# motor_controller_rev_3_0_6.net
KiCad netlist of a schematic drawn in EAGLE
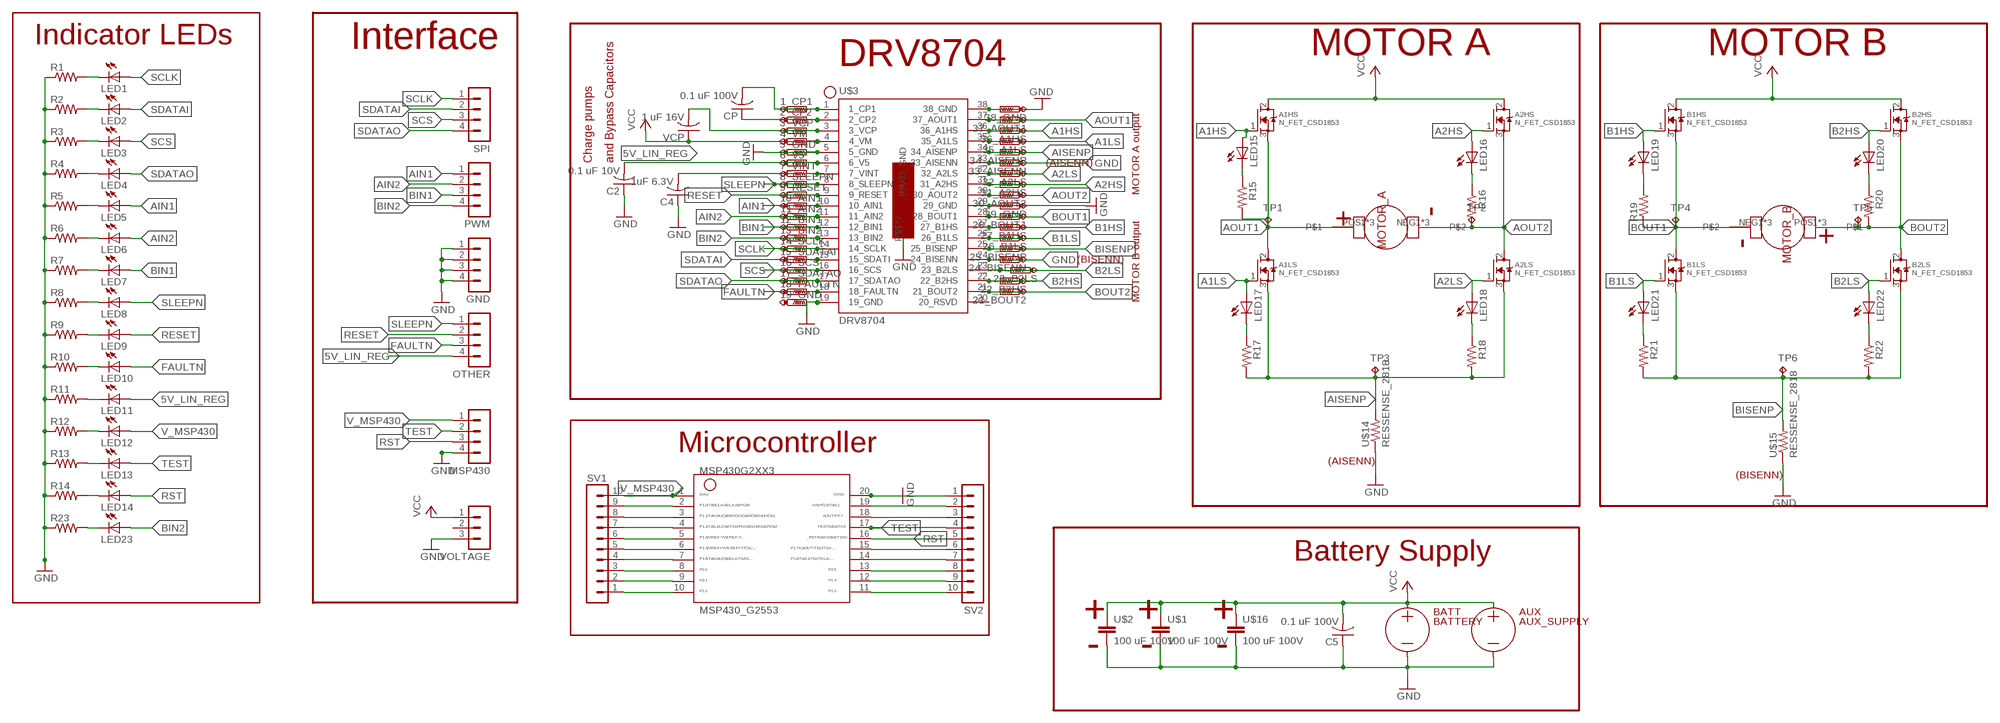
[diagram p0: schematic, sheet 1]

(export (version "E")
  (design (tool "Eeschema 10.0.6"))
  (components
    (comp (ref "1_CP1")
      (value "PTR1TP10R")
      (footprint "eagle-import:TP10R")
      (libsource (lib "eagle-import") (part "PTR1TP10R"))
    )
    (comp (ref "2_CP2")
      (value "PTR1TP10R")
      (footprint "eagle-import:TP10R")
      (libsource (lib "eagle-import") (part "PTR1TP10R"))
    )
    (comp (ref "3_VCP")
      (value "PTR1TP10R")
      (footprint "eagle-import:TP10R")
      (libsource (lib "eagle-import") (part "PTR1TP10R"))
    )
    (comp (ref "4_VM")
      (value "PTR1TP10R")
      (footprint "eagle-import:TP10R")
      (libsource (lib "eagle-import") (part "PTR1TP10R"))
    )
    (comp (ref "5_GND")
      (value "PTR1TP10R")
      (footprint "eagle-import:TP10R")
      (libsource (lib "eagle-import") (part "PTR1TP10R"))
    )
    (comp (ref "6_V5")
      (value "PTR1TP10R")
      (footprint "eagle-import:TP10R")
      (libsource (lib "eagle-import") (part "PTR1TP10R"))
    )
    (comp (ref "7_VINT")
      (value "PTR1TP10R")
      (footprint "eagle-import:TP10R")
      (libsource (lib "eagle-import") (part "PTR1TP10R"))
    )
    (comp (ref "8_SLEEPN")
      (value "PTR1TP10R")
      (footprint "eagle-import:TP10R")
      (libsource (lib "eagle-import") (part "PTR1TP10R"))
    )
    (comp (ref "9_RESET")
      (value "PTR1TP10R")
      (footprint "eagle-import:TP10R")
      (libsource (lib "eagle-import") (part "PTR1TP10R"))
    )
    (comp (ref "10_AIN1")
      (value "PTR1TP10R")
      (footprint "eagle-import:TP10R")
      (libsource (lib "eagle-import") (part "PTR1TP10R"))
    )
    (comp (ref "11_AIN2")
      (value "PTR1TP10R")
      (footprint "eagle-import:TP10R")
      (libsource (lib "eagle-import") (part "PTR1TP10R"))
    )
    (comp (ref "12_BIN1")
      (value "PTR1TP10R")
      (footprint "eagle-import:TP10R")
      (libsource (lib "eagle-import") (part "PTR1TP10R"))
    )
    (comp (ref "13_BIN2")
      (value "PTR1TP10R")
      (footprint "eagle-import:TP10R")
      (libsource (lib "eagle-import") (part "PTR1TP10R"))
    )
    (comp (ref "14_SCLK")
      (value "PTR1TP10R")
      (footprint "eagle-import:TP10R")
      (libsource (lib "eagle-import") (part "PTR1TP10R"))
    )
    (comp (ref "15_SDATAI")
      (value "PTR1TP10R")
      (footprint "eagle-import:TP10R")
      (libsource (lib "eagle-import") (part "PTR1TP10R"))
    )
    (comp (ref "16_SCS")
      (value "PTR1TP10R")
      (footprint "eagle-import:TP10R")
      (libsource (lib "eagle-import") (part "PTR1TP10R"))
    )
    (comp (ref "17_SDATAO")
      (value "PTR1TP10R")
      (footprint "eagle-import:TP10R")
      (libsource (lib "eagle-import") (part "PTR1TP10R"))
    )
    (comp (ref "18_FAULTN")
      (value "PTR1TP10R")
      (footprint "eagle-import:TP10R")
      (libsource (lib "eagle-import") (part "PTR1TP10R"))
    )
    (comp (ref "19_GND")
      (value "PTR1TP10R")
      (footprint "eagle-import:TP10R")
      (libsource (lib "eagle-import") (part "PTR1TP10R"))
    )
    (comp (ref "21_BOUT2")
      (value "PTR1TP10R")
      (footprint "eagle-import:TP10R")
      (libsource (lib "eagle-import") (part "PTR1TP10R"))
    )
    (comp (ref "22_B2HS")
      (value "PTR1TP10R")
      (footprint "eagle-import:TP10R")
      (libsource (lib "eagle-import") (part "PTR1TP10R"))
    )
    (comp (ref "23_B2LS")
      (value "PTR1TP10R")
      (footprint "eagle-import:TP10R")
      (libsource (lib "eagle-import") (part "PTR1TP10R"))
    )
    (comp (ref "24_BISENN")
      (value "PTR1TP10R")
      (footprint "eagle-import:TP10R")
      (libsource (lib "eagle-import") (part "PTR1TP10R"))
    )
    (comp (ref "25_BISENP")
      (value "PTR1TP10R")
      (footprint "eagle-import:TP10R")
      (libsource (lib "eagle-import") (part "PTR1TP10R"))
    )
    (comp (ref "26_B1LS")
      (value "PTR1TP10R")
      (footprint "eagle-import:TP10R")
      (libsource (lib "eagle-import") (part "PTR1TP10R"))
    )
    (comp (ref "27_B1HS")
      (value "PTR1TP10R")
      (footprint "eagle-import:TP10R")
      (libsource (lib "eagle-import") (part "PTR1TP10R"))
    )
    (comp (ref "28_BOUT1")
      (value "PTR1TP10R")
      (footprint "eagle-import:TP10R")
      (libsource (lib "eagle-import") (part "PTR1TP10R"))
    )
    (comp (ref "29_GND")
      (value "PTR1TP10R")
      (footprint "eagle-import:TP10R")
      (libsource (lib "eagle-import") (part "PTR1TP10R"))
    )
    (comp (ref "30_AOUT2")
      (value "PTR1TP10R")
      (footprint "eagle-import:TP10R")
      (libsource (lib "eagle-import") (part "PTR1TP10R"))
    )
    (comp (ref "31_A2HS")
      (value "PTR1TP10R")
      (footprint "eagle-import:TP10R")
      (libsource (lib "eagle-import") (part "PTR1TP10R"))
    )
    (comp (ref "32_A2LS")
      (value "PTR1TP10R")
      (footprint "eagle-import:TP10R")
      (libsource (lib "eagle-import") (part "PTR1TP10R"))
    )
    (comp (ref "33_AISENN")
      (value "PTR1TP10R")
      (footprint "eagle-import:TP10R")
      (libsource (lib "eagle-import") (part "PTR1TP10R"))
    )
    (comp (ref "34_AISENP")
      (value "PTR1TP10R")
      (footprint "eagle-import:TP10R")
      (libsource (lib "eagle-import") (part "PTR1TP10R"))
    )
    (comp (ref "35_A1LS")
      (value "PTR1TP10R")
      (footprint "eagle-import:TP10R")
      (libsource (lib "eagle-import") (part "PTR1TP10R"))
    )
    (comp (ref "36_A1HS")
      (value "PTR1TP10R")
      (footprint "eagle-import:TP10R")
      (libsource (lib "eagle-import") (part "PTR1TP10R"))
    )
    (comp (ref "37_AOUT1")
      (value "PTR1TP10R")
      (footprint "eagle-import:TP10R")
      (libsource (lib "eagle-import") (part "PTR1TP10R"))
    )
    (comp (ref "38_GND")
      (value "PTR1TP10R")
      (footprint "eagle-import:TP10R")
      (libsource (lib "eagle-import") (part "PTR1TP10R"))
    )
    (comp (ref "A1HS")
      (value "N_FET_CSD1853")
      (footprint "eagle-import:GDS_NFET")
      (libsource (lib "eagle-import") (part "N_FET_CSD1853"))
    )
    (comp (ref "A1LS")
      (value "N_FET_CSD1853")
      (footprint "eagle-import:GDS_NFET")
      (libsource (lib "eagle-import") (part "N_FET_CSD1853"))
    )
    (comp (ref "A2HS")
      (value "N_FET_CSD1853")
      (footprint "eagle-import:GDS_NFET")
      (libsource (lib "eagle-import") (part "N_FET_CSD1853"))
    )
    (comp (ref "A2LS")
      (value "N_FET_CSD1853")
      (footprint "eagle-import:GDS_NFET")
      (libsource (lib "eagle-import") (part "N_FET_CSD1853"))
    )
    (comp (ref "AUX")
      (value "AUX_SUPPLY")
      (footprint "eagle-import:PP14-45_RIGHT_ANGLE")
      (libsource (lib "eagle-import") (part "AUX_SUPPLY"))
    )
    (comp (ref "B1HS")
      (value "N_FET_CSD1853")
      (footprint "eagle-import:GDS_NFET")
      (libsource (lib "eagle-import") (part "N_FET_CSD1853"))
    )
    (comp (ref "B1LS")
      (value "N_FET_CSD1853")
      (footprint "eagle-import:GDS_NFET")
      (libsource (lib "eagle-import") (part "N_FET_CSD1853"))
    )
    (comp (ref "B2HS")
      (value "N_FET_CSD1853")
      (footprint "eagle-import:GDS_NFET")
      (libsource (lib "eagle-import") (part "N_FET_CSD1853"))
    )
    (comp (ref "B2LS")
      (value "N_FET_CSD1853")
      (footprint "eagle-import:GDS_NFET")
      (libsource (lib "eagle-import") (part "N_FET_CSD1853"))
    )
    (comp (ref "BATT")
      (value "BATTERY")
      (footprint "eagle-import:SB50POWER_CLAW")
      (libsource (lib "eagle-import") (part "BATTERY"))
    )
    (comp (ref "C2")
      (value "0.1 uF 10V")
      (footprint "eagle-import:C0805K")
      (libsource (lib "eagle-import") (part "C-USC0805K"))
    )
    (comp (ref "C4")
      (value "1uF 6.3V")
      (footprint "eagle-import:C0805K")
      (libsource (lib "eagle-import") (part "C-USC0805K"))
    )
    (comp (ref "C5")
      (value "0.1 uF 100V")
      (footprint "eagle-import:C0805K")
      (libsource (lib "eagle-import") (part "C-USC0805K"))
    )
    (comp (ref "CP")
      (value "0.1 uF 100V")
      (footprint "eagle-import:C0805K")
      (libsource (lib "eagle-import") (part "C-USC0805K"))
    )
    (comp (ref "GND")
      (value "MA04-1")
      (footprint "eagle-import:MA04-1")
      (libsource (lib "eagle-import") (part "MA04-1"))
    )
    (comp (ref "LED1")
      (value "LEDCHIPLED_0805")
      (footprint "eagle-import:CHIPLED_0805")
      (libsource (lib "eagle-import") (part "LEDCHIPLED_0805"))
    )
    (comp (ref "LED2")
      (value "LEDCHIPLED_0805")
      (footprint "eagle-import:CHIPLED_0805")
      (libsource (lib "eagle-import") (part "LEDCHIPLED_0805"))
    )
    (comp (ref "LED3")
      (value "LEDCHIPLED_0805")
      (footprint "eagle-import:CHIPLED_0805")
      (libsource (lib "eagle-import") (part "LEDCHIPLED_0805"))
    )
    (comp (ref "LED4")
      (value "LEDCHIPLED_0805")
      (footprint "eagle-import:CHIPLED_0805")
      (libsource (lib "eagle-import") (part "LEDCHIPLED_0805"))
    )
    (comp (ref "LED5")
      (value "LEDCHIPLED_0805")
      (footprint "eagle-import:CHIPLED_0805")
      (libsource (lib "eagle-import") (part "LEDCHIPLED_0805"))
    )
    (comp (ref "LED6")
      (value "LEDCHIPLED_0805")
      (footprint "eagle-import:CHIPLED_0805")
      (libsource (lib "eagle-import") (part "LEDCHIPLED_0805"))
    )
    (comp (ref "LED7")
      (value "LEDCHIPLED_0805")
      (footprint "eagle-import:CHIPLED_0805")
      (libsource (lib "eagle-import") (part "LEDCHIPLED_0805"))
    )
    (comp (ref "LED8")
      (value "LEDCHIPLED_0805")
      (footprint "eagle-import:CHIPLED_0805")
      (libsource (lib "eagle-import") (part "LEDCHIPLED_0805"))
    )
    (comp (ref "LED9")
      (value "LEDCHIPLED_0805")
      (footprint "eagle-import:CHIPLED_0805")
      (libsource (lib "eagle-import") (part "LEDCHIPLED_0805"))
    )
    (comp (ref "LED10")
      (value "LEDCHIPLED_0805")
      (footprint "eagle-import:CHIPLED_0805")
      (libsource (lib "eagle-import") (part "LEDCHIPLED_0805"))
    )
    (comp (ref "LED11")
      (value "LEDCHIPLED_0805")
      (footprint "eagle-import:CHIPLED_0805")
      (libsource (lib "eagle-import") (part "LEDCHIPLED_0805"))
    )
    (comp (ref "LED12")
      (value "LEDCHIPLED_0805")
      (footprint "eagle-import:CHIPLED_0805")
      (libsource (lib "eagle-import") (part "LEDCHIPLED_0805"))
    )
    (comp (ref "LED13")
      (value "LEDCHIPLED_0805")
      (footprint "eagle-import:CHIPLED_0805")
      (libsource (lib "eagle-import") (part "LEDCHIPLED_0805"))
    )
    (comp (ref "LED14")
      (value "LEDCHIPLED_0805")
      (footprint "eagle-import:CHIPLED_0805")
      (libsource (lib "eagle-import") (part "LEDCHIPLED_0805"))
    )
    (comp (ref "LED15")
      (value "LEDCHIPLED_0805")
      (footprint "eagle-import:CHIPLED_0805")
      (libsource (lib "eagle-import") (part "LEDCHIPLED_0805"))
    )
    (comp (ref "LED16")
      (value "LEDCHIPLED_0805")
      (footprint "eagle-import:CHIPLED_0805")
      (libsource (lib "eagle-import") (part "LEDCHIPLED_0805"))
    )
    (comp (ref "LED17")
      (value "LEDCHIPLED_0805")
      (footprint "eagle-import:CHIPLED_0805")
      (libsource (lib "eagle-import") (part "LEDCHIPLED_0805"))
    )
    (comp (ref "LED18")
      (value "LEDCHIPLED_0805")
      (footprint "eagle-import:CHIPLED_0805")
      (libsource (lib "eagle-import") (part "LEDCHIPLED_0805"))
    )
    (comp (ref "LED19")
      (value "LEDCHIPLED_0805")
      (footprint "eagle-import:CHIPLED_0805")
      (libsource (lib "eagle-import") (part "LEDCHIPLED_0805"))
    )
    (comp (ref "LED20")
      (value "LEDCHIPLED_0805")
      (footprint "eagle-import:CHIPLED_0805")
      (libsource (lib "eagle-import") (part "LEDCHIPLED_0805"))
    )
    (comp (ref "LED21")
      (value "LEDCHIPLED_0805")
      (footprint "eagle-import:CHIPLED_0805")
      (libsource (lib "eagle-import") (part "LEDCHIPLED_0805"))
    )
    (comp (ref "LED22")
      (value "LEDCHIPLED_0805")
      (footprint "eagle-import:CHIPLED_0805")
      (libsource (lib "eagle-import") (part "LEDCHIPLED_0805"))
    )
    (comp (ref "LED23")
      (value "LEDCHIPLED_0805")
      (footprint "eagle-import:CHIPLED_0805")
      (libsource (lib "eagle-import") (part "LEDCHIPLED_0805"))
    )
    (comp (ref "MOTOR_A")
      (value "MOTOR")
      (footprint "eagle-import:SB50POWER_CLAW")
      (libsource (lib "eagle-import") (part "MOTOR"))
    )
    (comp (ref "MOTOR_B")
      (value "MOTOR")
      (footprint "eagle-import:SB50POWER_CLAW")
      (libsource (lib "eagle-import") (part "MOTOR"))
    )
    (comp (ref "MSP430")
      (value "MA04-1")
      (footprint "eagle-import:MA04-1")
      (libsource (lib "eagle-import") (part "MA04-1"))
    )
    (comp (ref "MSP430_G2553")
      (value "G2XX3---N20")
      (footprint "eagle-import:N20")
      (libsource (lib "eagle-import") (part "G2XX3---N20"))
    )
    (comp (ref "OTHER")
      (value "MA04-1")
      (footprint "eagle-import:MA04-1")
      (libsource (lib "eagle-import") (part "MA04-1"))
    )
    (comp (ref "PWM")
      (value "MA04-1")
      (footprint "eagle-import:MA04-1")
      (libsource (lib "eagle-import") (part "MA04-1"))
    )
    (comp (ref "R1")
      (value "R-US_R0805")
      (footprint "eagle-import:R0805")
      (libsource (lib "eagle-import") (part "R-US_R0805"))
    )
    (comp (ref "R2")
      (value "R-US_R0805")
      (footprint "eagle-import:R0805")
      (libsource (lib "eagle-import") (part "R-US_R0805"))
    )
    (comp (ref "R3")
      (value "R-US_R0805")
      (footprint "eagle-import:R0805")
      (libsource (lib "eagle-import") (part "R-US_R0805"))
    )
    (comp (ref "R4")
      (value "R-US_R0805")
      (footprint "eagle-import:R0805")
      (libsource (lib "eagle-import") (part "R-US_R0805"))
    )
    (comp (ref "R5")
      (value "R-US_R0805")
      (footprint "eagle-import:R0805")
      (libsource (lib "eagle-import") (part "R-US_R0805"))
    )
    (comp (ref "R6")
      (value "R-US_R0805")
      (footprint "eagle-import:R0805")
      (libsource (lib "eagle-import") (part "R-US_R0805"))
    )
    (comp (ref "R7")
      (value "R-US_R0805")
      (footprint "eagle-import:R0805")
      (libsource (lib "eagle-import") (part "R-US_R0805"))
    )
    (comp (ref "R8")
      (value "R-US_R0805")
      (footprint "eagle-import:R0805")
      (libsource (lib "eagle-import") (part "R-US_R0805"))
    )
    (comp (ref "R9")
      (value "R-US_R0805")
      (footprint "eagle-import:R0805")
      (libsource (lib "eagle-import") (part "R-US_R0805"))
    )
    (comp (ref "R10")
      (value "R-US_R0805")
      (footprint "eagle-import:R0805")
      (libsource (lib "eagle-import") (part "R-US_R0805"))
    )
    (comp (ref "R11")
      (value "R-US_R0805")
      (footprint "eagle-import:R0805")
      (libsource (lib "eagle-import") (part "R-US_R0805"))
    )
    (comp (ref "R12")
      (value "R-US_R0805")
      (footprint "eagle-import:R0805")
      (libsource (lib "eagle-import") (part "R-US_R0805"))
    )
    (comp (ref "R13")
      (value "R-US_R0805")
      (footprint "eagle-import:R0805")
      (libsource (lib "eagle-import") (part "R-US_R0805"))
    )
    (comp (ref "R14")
      (value "R-US_R0805")
      (footprint "eagle-import:R0805")
      (libsource (lib "eagle-import") (part "R-US_R0805"))
    )
    (comp (ref "R15")
      (value "R-US_R0805")
      (footprint "eagle-import:R0805")
      (libsource (lib "eagle-import") (part "R-US_R0805"))
    )
    (comp (ref "R16")
      (value "R-US_R0805")
      (footprint "eagle-import:R0805")
      (libsource (lib "eagle-import") (part "R-US_R0805"))
    )
    (comp (ref "R17")
      (value "R-US_R0805")
      (footprint "eagle-import:R0805")
      (libsource (lib "eagle-import") (part "R-US_R0805"))
    )
    (comp (ref "R18")
      (value "R-US_R0805")
      (footprint "eagle-import:R0805")
      (libsource (lib "eagle-import") (part "R-US_R0805"))
    )
    (comp (ref "R19")
      (value "R-US_R0805")
      (footprint "eagle-import:R0805")
      (libsource (lib "eagle-import") (part "R-US_R0805"))
    )
    (comp (ref "R20")
      (value "R-US_R0805")
      (footprint "eagle-import:R0805")
      (libsource (lib "eagle-import") (part "R-US_R0805"))
    )
    (comp (ref "R21")
      (value "R-US_R0805")
      (footprint "eagle-import:R0805")
      (libsource (lib "eagle-import") (part "R-US_R0805"))
    )
    (comp (ref "R22")
      (value "R-US_R0805")
      (footprint "eagle-import:R0805")
      (libsource (lib "eagle-import") (part "R-US_R0805"))
    )
    (comp (ref "R23")
      (value "R-US_R0805")
      (footprint "eagle-import:R0805")
      (libsource (lib "eagle-import") (part "R-US_R0805"))
    )
    (comp (ref "SPI")
      (value "MA04-1")
      (footprint "eagle-import:MA04-1")
      (libsource (lib "eagle-import") (part "MA04-1"))
    )
    (comp (ref "SV1")
      (value "MA10-1")
      (footprint "eagle-import:MA10-1")
      (libsource (lib "eagle-import") (part "MA10-1"))
    )
    (comp (ref "SV2")
      (value "MA10-1")
      (footprint "eagle-import:MA10-1")
      (libsource (lib "eagle-import") (part "MA10-1"))
    )
    (comp (ref "TP1")
      (value "TPB2,54")
      (footprint "eagle-import:B2,54")
      (libsource (lib "eagle-import") (part "TPB2,54"))
    )
    (comp (ref "TP2")
      (value "TPB2,54")
      (footprint "eagle-import:B2,54")
      (libsource (lib "eagle-import") (part "TPB2,54"))
    )
    (comp (ref "TP3")
      (value "TPB2,54")
      (footprint "eagle-import:B2,54")
      (libsource (lib "eagle-import") (part "TPB2,54"))
    )
    (comp (ref "TP4")
      (value "TPB2,54")
      (footprint "eagle-import:B2,54")
      (libsource (lib "eagle-import") (part "TPB2,54"))
    )
    (comp (ref "TP5")
      (value "TPB2,54")
      (footprint "eagle-import:B2,54")
      (libsource (lib "eagle-import") (part "TPB2,54"))
    )
    (comp (ref "TP6")
      (value "TPB2,54")
      (footprint "eagle-import:B2,54")
      (libsource (lib "eagle-import") (part "TPB2,54"))
    )
    (comp (ref "U$1")
      (value "100 uF 100V")
      (footprint "eagle-import:UCY_HD_CAP")
      (libsource (lib "eagle-import") (part "LARGE_CAP"))
    )
    (comp (ref "U$2")
      (value "100 uF 100V")
      (footprint "eagle-import:UCY_HD_CAP")
      (libsource (lib "eagle-import") (part "LARGE_CAP"))
    )
    (comp (ref "U$3")
      (value "DRV8704")
      (footprint "eagle-import:HTSSOP-38")
      (libsource (lib "eagle-import") (part "DRV8704"))
    )
    (comp (ref "U$14")
      (value "RESSENSE_2818")
      (footprint "eagle-import:2818_WITH_VIA")
      (libsource (lib "eagle-import") (part "RESSENSE_2818"))
    )
    (comp (ref "U$15")
      (value "RESSENSE_2818")
      (footprint "eagle-import:2818_WITH_VIA")
      (libsource (lib "eagle-import") (part "RESSENSE_2818"))
    )
    (comp (ref "U$16")
      (value "100 uF 100V")
      (footprint "eagle-import:UCY_HD_CAP")
      (libsource (lib "eagle-import") (part "LARGE_CAP"))
    )
    (comp (ref "VCP")
      (value "1 uF 16V")
      (footprint "eagle-import:C0805K")
      (libsource (lib "eagle-import") (part "C-USC0805K"))
    )
    (comp (ref "VOLTAGE")
      (value "MA03-1")
      (footprint "eagle-import:MA03-1")
      (libsource (lib "eagle-import") (part "MA03-1"))
    )
  )
  (nets
    (net (code "1") (name "5V_LIN_REG") (class "Default")
      (node (ref "6_V5") (pin "TP") (pinfunction "TP_TP") (pintype "input"))
      (node (ref "C2") (pin "2") (pinfunction "2_2") (pintype "passive"))
      (node (ref "LED11") (pin "A") (pinfunction "A_A") (pintype "passive"))
      (node (ref "OTHER") (pin "4") (pinfunction "4_4") (pintype "passive"))
      (node (ref "U$3") (pin "6") (pinfunction "6_V5_6") (pintype "bidirectional"))
    )
    (net (code "2") (name "A1HS") (class "Default")
      (node (ref "36_A1HS") (pin "TP") (pinfunction "TP_TP") (pintype "input"))
      (node (ref "A1HS") (pin "1") (pinfunction "G_1") (pintype "bidirectional"))
      (node (ref "LED15") (pin "A") (pinfunction "A_A") (pintype "passive"))
      (node (ref "U$3") (pin "36") (pinfunction "36_A1HS_36") (pintype "bidirectional"))
    )
    (net (code "3") (name "A1LS") (class "Default")
      (node (ref "35_A1LS") (pin "TP") (pinfunction "TP_TP") (pintype "input"))
      (node (ref "A1LS") (pin "1") (pinfunction "G_1") (pintype "bidirectional"))
      (node (ref "LED17") (pin "A") (pinfunction "A_A") (pintype "passive"))
      (node (ref "U$3") (pin "35") (pinfunction "35_A1LS_35") (pintype "bidirectional"))
    )
    (net (code "4") (name "A2HS") (class "Default")
      (node (ref "31_A2HS") (pin "TP") (pinfunction "TP_TP") (pintype "input"))
      (node (ref "A2HS") (pin "1") (pinfunction "G_1") (pintype "bidirectional"))
      (node (ref "LED16") (pin "A") (pinfunction "A_A") (pintype "passive"))
      (node (ref "U$3") (pin "31") (pinfunction "31_A2HS_31") (pintype "bidirectional"))
    )
    (net (code "5") (name "A2LS") (class "Default")
      (node (ref "32_A2LS") (pin "TP") (pinfunction "TP_TP") (pintype "input"))
      (node (ref "A2LS") (pin "1") (pinfunction "G_1") (pintype "bidirectional"))
      (node (ref "LED18") (pin "A") (pinfunction "A_A") (pintype "passive"))
      (node (ref "U$3") (pin "32") (pinfunction "32_A2LS_32") (pintype "bidirectional"))
    )
    (net (code "6") (name "AIN1") (class "Default")
      (node (ref "10_AIN1") (pin "TP") (pinfunction "TP_TP") (pintype "input"))
      (node (ref "LED5") (pin "A") (pinfunction "A_A") (pintype "passive"))
      (node (ref "PWM") (pin "1") (pinfunction "1_1") (pintype "passive"))
      (node (ref "U$3") (pin "10") (pinfunction "10_AIN1_10") (pintype "bidirectional"))
    )
    (net (code "7") (name "AIN2") (class "Default")
      (node (ref "11_AIN2") (pin "TP") (pinfunction "TP_TP") (pintype "input"))
      (node (ref "LED6") (pin "A") (pinfunction "A_A") (pintype "passive"))
      (node (ref "PWM") (pin "2") (pinfunction "2_2") (pintype "passive"))
      (node (ref "U$3") (pin "11") (pinfunction "11_AIN2_11") (pintype "bidirectional"))
    )
    (net (code "8") (name "AISENP") (class "Default")
      (node (ref "34_AISENP") (pin "TP") (pinfunction "TP_TP") (pintype "input"))
      (node (ref "A1LS") (pin "3") (pinfunction "S_3") (pintype "bidirectional"))
      (node (ref "A2LS") (pin "3") (pinfunction "S_3") (pintype "bidirectional"))
      (node (ref "R17") (pin "2") (pinfunction "2_2") (pintype "passive"))
      (node (ref "R18") (pin "2") (pinfunction "2_2") (pintype "passive"))
      (node (ref "TP3") (pin "TP") (pinfunction "TP_TP") (pintype "input"))
      (node (ref "U$14") (pin "P$2") (pinfunction "2_P$2") (pintype "passive"))
      (node (ref "U$14") (pin "P2.2") (pinfunction "2_P2.2") (pintype "passive"))
      (node (ref "U$3") (pin "34") (pinfunction "34_AISENP_34") (pintype "bidirectional"))
    )
    (net (code "9") (name "AOUT1") (class "Default")
      (node (ref "37_AOUT1") (pin "TP") (pinfunction "TP_TP") (pintype "input"))
      (node (ref "A1HS") (pin "3") (pinfunction "S_3") (pintype "bidirectional"))
      (node (ref "A1LS") (pin "2") (pinfunction "D_2") (pintype "bidirectional"))
      (node (ref "MOTOR_A") (pin "POS1") (pinfunction "P$1_POS1") (pintype "bidirectional"))
      (node (ref "MOTOR_A") (pin "POS2") (pinfunction "P$1_POS2") (pintype "bidirectional"))
      (node (ref "MOTOR_A") (pin "POS3") (pinfunction "P$1_POS3") (pintype "bidirectional"))
      (node (ref "R15") (pin "2") (pinfunction "2_2") (pintype "passive"))
      (node (ref "TP1") (pin "TP") (pinfunction "TP_TP") (pintype "input"))
      (node (ref "U$3") (pin "37") (pinfunction "37_AOUT1_37") (pintype "bidirectional"))
    )
    (net (code "10") (name "AOUT2") (class "Default")
      (node (ref "30_AOUT2") (pin "TP") (pinfunction "TP_TP") (pintype "input"))
      (node (ref "A2HS") (pin "3") (pinfunction "S_3") (pintype "bidirectional"))
      (node (ref "A2LS") (pin "2") (pinfunction "D_2") (pintype "bidirectional"))
      (node (ref "MOTOR_A") (pin "NEG1") (pinfunction "P$2_NEG1") (pintype "bidirectional"))
      (node (ref "MOTOR_A") (pin "NEG2") (pinfunction "P$2_NEG2") (pintype "bidirectional"))
      (node (ref "MOTOR_A") (pin "NEG3") (pinfunction "P$2_NEG3") (pintype "bidirectional"))
      (node (ref "R16") (pin "2") (pinfunction "2_2") (pintype "passive"))
      (node (ref "TP2") (pin "TP") (pinfunction "TP_TP") (pintype "input"))
      (node (ref "U$3") (pin "30") (pinfunction "30_AOUT2_30") (pintype "bidirectional"))
    )
    (net (code "11") (name "B1HS") (class "Default")
      (node (ref "27_B1HS") (pin "TP") (pinfunction "TP_TP") (pintype "input"))
      (node (ref "B1HS") (pin "1") (pinfunction "G_1") (pintype "bidirectional"))
      (node (ref "LED19") (pin "A") (pinfunction "A_A") (pintype "passive"))
      (node (ref "U$3") (pin "27") (pinfunction "27_B1HS_27") (pintype "bidirectional"))
    )
    (net (code "12") (name "B1LS") (class "Default")
      (node (ref "26_B1LS") (pin "TP") (pinfunction "TP_TP") (pintype "input"))
      (node (ref "B1LS") (pin "1") (pinfunction "G_1") (pintype "bidirectional"))
      (node (ref "LED21") (pin "A") (pinfunction "A_A") (pintype "passive"))
      (node (ref "U$3") (pin "26") (pinfunction "26_B1LS_26") (pintype "bidirectional"))
    )
    (net (code "13") (name "B2HS") (class "Default")
      (node (ref "22_B2HS") (pin "TP") (pinfunction "TP_TP") (pintype "input"))
      (node (ref "B2HS") (pin "1") (pinfunction "G_1") (pintype "bidirectional"))
      (node (ref "LED20") (pin "A") (pinfunction "A_A") (pintype "passive"))
      (node (ref "U$3") (pin "22") (pinfunction "22_B2HS_22") (pintype "bidirectional"))
    )
    (net (code "14") (name "B2LS") (class "Default")
      (node (ref "23_B2LS") (pin "TP") (pinfunction "TP_TP") (pintype "input"))
      (node (ref "B2LS") (pin "1") (pinfunction "G_1") (pintype "bidirectional"))
      (node (ref "LED22") (pin "A") (pinfunction "A_A") (pintype "passive"))
      (node (ref "U$3") (pin "23") (pinfunction "23_B2LS_23") (pintype "bidirectional"))
    )
    (net (code "15") (name "BIN1") (class "Default")
      (node (ref "12_BIN1") (pin "TP") (pinfunction "TP_TP") (pintype "input"))
      (node (ref "LED7") (pin "A") (pinfunction "A_A") (pintype "passive"))
      (node (ref "PWM") (pin "3") (pinfunction "3_3") (pintype "passive"))
      (node (ref "U$3") (pin "12") (pinfunction "12_BIN1_12") (pintype "bidirectional"))
    )
    (net (code "16") (name "BIN2") (class "Default")
      (node (ref "13_BIN2") (pin "TP") (pinfunction "TP_TP") (pintype "input"))
      (node (ref "LED23") (pin "A") (pinfunction "A_A") (pintype "passive"))
      (node (ref "PWM") (pin "4") (pinfunction "4_4") (pintype "passive"))
      (node (ref "U$3") (pin "13") (pinfunction "13_BIN2_13") (pintype "bidirectional"))
    )
    (net (code "17") (name "BISENP") (class "Default")
      (node (ref "25_BISENP") (pin "TP") (pinfunction "TP_TP") (pintype "input"))
      (node (ref "B1LS") (pin "3") (pinfunction "S_3") (pintype "bidirectional"))
      (node (ref "B2LS") (pin "3") (pinfunction "S_3") (pintype "bidirectional"))
      (node (ref "R21") (pin "2") (pinfunction "2_2") (pintype "passive"))
      (node (ref "R22") (pin "2") (pinfunction "2_2") (pintype "passive"))
      (node (ref "TP6") (pin "TP") (pinfunction "TP_TP") (pintype "input"))
      (node (ref "U$15") (pin "P$2") (pinfunction "2_P$2") (pintype "passive"))
      (node (ref "U$15") (pin "P2.2") (pinfunction "2_P2.2") (pintype "passive"))
      (node (ref "U$3") (pin "25") (pinfunction "25_BISENP_25") (pintype "bidirectional"))
    )
    (net (code "18") (name "BOUT1") (class "Default")
      (node (ref "28_BOUT1") (pin "TP") (pinfunction "TP_TP") (pintype "input"))
      (node (ref "B1HS") (pin "3") (pinfunction "S_3") (pintype "bidirectional"))
      (node (ref "B1LS") (pin "2") (pinfunction "D_2") (pintype "bidirectional"))
      (node (ref "MOTOR_B") (pin "NEG1") (pinfunction "P$2_NEG1") (pintype "bidirectional"))
      (node (ref "MOTOR_B") (pin "NEG2") (pinfunction "P$2_NEG2") (pintype "bidirectional"))
      (node (ref "MOTOR_B") (pin "NEG3") (pinfunction "P$2_NEG3") (pintype "bidirectional"))
      (node (ref "R19") (pin "1") (pinfunction "1_1") (pintype "passive"))
      (node (ref "TP4") (pin "TP") (pinfunction "TP_TP") (pintype "input"))
      (node (ref "U$3") (pin "28") (pinfunction "28_BOUT1_28") (pintype "bidirectional"))
    )
    (net (code "19") (name "BOUT2") (class "Default")
      (node (ref "21_BOUT2") (pin "TP") (pinfunction "TP_TP") (pintype "input"))
      (node (ref "B2HS") (pin "3") (pinfunction "S_3") (pintype "bidirectional"))
      (node (ref "B2LS") (pin "2") (pinfunction "D_2") (pintype "bidirectional"))
      (node (ref "MOTOR_B") (pin "POS1") (pinfunction "P$1_POS1") (pintype "bidirectional"))
      (node (ref "MOTOR_B") (pin "POS2") (pinfunction "P$1_POS2") (pintype "bidirectional"))
      (node (ref "MOTOR_B") (pin "POS3") (pinfunction "P$1_POS3") (pintype "bidirectional"))
      (node (ref "R20") (pin "2") (pinfunction "2_2") (pintype "passive"))
      (node (ref "TP5") (pin "TP") (pinfunction "TP_TP") (pintype "input"))
      (node (ref "U$3") (pin "21") (pinfunction "21_BOUT2_21") (pintype "bidirectional"))
    )
    (net (code "20") (name "FAULTN") (class "Default")
      (node (ref "18_FAULTN") (pin "TP") (pinfunction "TP_TP") (pintype "input"))
      (node (ref "LED10") (pin "A") (pinfunction "A_A") (pintype "passive"))
      (node (ref "OTHER") (pin "3") (pinfunction "3_3") (pintype "passive"))
      (node (ref "U$3") (pin "18") (pinfunction "18_FAULTN_18") (pintype "bidirectional"))
    )
    (net (code "21") (name "GND") (class "Default")
      (node (ref "19_GND") (pin "TP") (pinfunction "TP_TP") (pintype "input"))
      (node (ref "24_BISENN") (pin "TP") (pinfunction "TP_TP") (pintype "input"))
      (node (ref "29_GND") (pin "TP") (pinfunction "TP_TP") (pintype "input"))
      (node (ref "33_AISENN") (pin "TP") (pinfunction "TP_TP") (pintype "input"))
      (node (ref "38_GND") (pin "TP") (pinfunction "TP_TP") (pintype "input"))
      (node (ref "5_GND") (pin "TP") (pinfunction "TP_TP") (pintype "input"))
      (node (ref "AUX") (pin "P$1") (pinfunction "-_P$1") (pintype "passive"))
      (node (ref "BATT") (pin "NEG1") (pinfunction "-_NEG1") (pintype "passive"))
      (node (ref "BATT") (pin "NEG2") (pinfunction "-_NEG2") (pintype "passive"))
      (node (ref "BATT") (pin "NEG3") (pinfunction "-_NEG3") (pintype "passive"))
      (node (ref "C2") (pin "1") (pinfunction "1_1") (pintype "passive"))
      (node (ref "C4") (pin "1") (pinfunction "1_1") (pintype "passive"))
      (node (ref "C5") (pin "1") (pinfunction "1_1") (pintype "passive"))
      (node (ref "GND") (pin "1") (pinfunction "1_1") (pintype "passive"))
      (node (ref "GND") (pin "2") (pinfunction "2_2") (pintype "passive"))
      (node (ref "GND") (pin "3") (pinfunction "3_3") (pintype "passive"))
      (node (ref "GND") (pin "4") (pinfunction "4_4") (pintype "passive"))
      (node (ref "MSP430") (pin "4") (pinfunction "4_4") (pintype "passive"))
      (node (ref "MSP430_G2553") (pin "20") (pinfunction "20_20") (pintype "bidirectional"))
      (node (ref "R1") (pin "1") (pinfunction "1_1") (pintype "passive"))
      (node (ref "R10") (pin "1") (pinfunction "1_1") (pintype "passive"))
      (node (ref "R11") (pin "1") (pinfunction "1_1") (pintype "passive"))
      (node (ref "R12") (pin "1") (pinfunction "1_1") (pintype "passive"))
      (node (ref "R13") (pin "1") (pinfunction "1_1") (pintype "passive"))
      (node (ref "R14") (pin "1") (pinfunction "1_1") (pintype "passive"))
      (node (ref "R2") (pin "1") (pinfunction "1_1") (pintype "passive"))
      (node (ref "R23") (pin "1") (pinfunction "1_1") (pintype "passive"))
      (node (ref "R3") (pin "1") (pinfunction "1_1") (pintype "passive"))
      (node (ref "R4") (pin "1") (pinfunction "1_1") (pintype "passive"))
      (node (ref "R5") (pin "1") (pinfunction "1_1") (pintype "passive"))
      (node (ref "R6") (pin "1") (pinfunction "1_1") (pintype "passive"))
      (node (ref "R7") (pin "1") (pinfunction "1_1") (pintype "passive"))
      (node (ref "R8") (pin "1") (pinfunction "1_1") (pintype "passive"))
      (node (ref "R9") (pin "1") (pinfunction "1_1") (pintype "passive"))
      (node (ref "SV2") (pin "1") (pinfunction "1_1") (pintype "passive"))
      (node (ref "U$1") (pin "-") (pinfunction "-_-") (pintype "passive"))
      (node (ref "U$14") (pin "P$1") (pinfunction "1_P$1") (pintype "passive"))
      (node (ref "U$14") (pin "P1.1") (pinfunction "1_P1.1") (pintype "passive"))
      (node (ref "U$15") (pin "P$1") (pinfunction "1_P$1") (pintype "passive"))
      (node (ref "U$15") (pin "P1.1") (pinfunction "1_P1.1") (pintype "passive"))
      (node (ref "U$16") (pin "-") (pinfunction "-_-") (pintype "passive"))
      (node (ref "U$2") (pin "-") (pinfunction "-_-") (pintype "passive"))
      (node (ref "U$3") (pin "19") (pinfunction "19_GND_19") (pintype "bidirectional"))
      (node (ref "U$3") (pin "24") (pinfunction "24_BISENN_24") (pintype "bidirectional"))
      (node (ref "U$3") (pin "29") (pinfunction "29_GND_29") (pintype "bidirectional"))
      (node (ref "U$3") (pin "33") (pinfunction "33_AISENN_33") (pintype "bidirectional"))
      (node (ref "U$3") (pin "38") (pinfunction "38_GND_38") (pintype "bidirectional"))
      (node (ref "U$3") (pin "5") (pinfunction "5_GND_5") (pintype "bidirectional"))
      (node (ref "U$3") (pin "P$1") (pinfunction "PPAD_GND_P$1") (pintype "bidirectional"))
      (node (ref "U$3") (pin "P$2") (pinfunction "PPAD_GND_P$2") (pintype "bidirectional"))
      (node (ref "U$3") (pin "P$3") (pinfunction "PPAD_GND_P$3") (pintype "bidirectional"))
      (node (ref "U$3") (pin "P$4") (pinfunction "PPAD_GND_P$4") (pintype "bidirectional"))
      (node (ref "U$3") (pin "PPAD0") (pinfunction "PPAD_GND_PPAD0") (pintype "bidirectional"))
      (node (ref "U$3") (pin "PPAD1") (pinfunction "PPAD_GND_PPAD1") (pintype "bidirectional"))
      (node (ref "U$3") (pin "PPAD2") (pinfunction "PPAD_GND_PPAD2") (pintype "bidirectional"))
      (node (ref "VOLTAGE") (pin "3") (pinfunction "3_3") (pintype "passive"))
    )
    (net (code "22") (name "Net-(LED1-PadC)") (class "Default")
      (node (ref "LED1") (pin "C") (pinfunction "C_C") (pintype "passive"))
      (node (ref "R1") (pin "2") (pinfunction "2_2") (pintype "passive"))
    )
    (net (code "23") (name "Net-(LED2-PadC)") (class "Default")
      (node (ref "LED2") (pin "C") (pinfunction "C_C") (pintype "passive"))
      (node (ref "R2") (pin "2") (pinfunction "2_2") (pintype "passive"))
    )
    (net (code "24") (name "Net-(LED3-PadC)") (class "Default")
      (node (ref "LED3") (pin "C") (pinfunction "C_C") (pintype "passive"))
      (node (ref "R3") (pin "2") (pinfunction "2_2") (pintype "passive"))
    )
    (net (code "25") (name "Net-(LED4-PadC)") (class "Default")
      (node (ref "LED4") (pin "C") (pinfunction "C_C") (pintype "passive"))
      (node (ref "R4") (pin "2") (pinfunction "2_2") (pintype "passive"))
    )
    (net (code "26") (name "Net-(LED5-PadC)") (class "Default")
      (node (ref "LED5") (pin "C") (pinfunction "C_C") (pintype "passive"))
      (node (ref "R5") (pin "2") (pinfunction "2_2") (pintype "passive"))
    )
    (net (code "27") (name "Net-(LED6-PadC)") (class "Default")
      (node (ref "LED6") (pin "C") (pinfunction "C_C") (pintype "passive"))
      (node (ref "R6") (pin "2") (pinfunction "2_2") (pintype "passive"))
    )
    (net (code "28") (name "Net-(LED7-PadC)") (class "Default")
      (node (ref "LED7") (pin "C") (pinfunction "C_C") (pintype "passive"))
      (node (ref "R7") (pin "2") (pinfunction "2_2") (pintype "passive"))
    )
    (net (code "29") (name "Net-(LED8-PadC)") (class "Default")
      (node (ref "LED8") (pin "C") (pinfunction "C_C") (pintype "passive"))
      (node (ref "R8") (pin "2") (pinfunction "2_2") (pintype "passive"))
    )
    (net (code "30") (name "Net-(LED9-PadC)") (class "Default")
      (node (ref "LED9") (pin "C") (pinfunction "C_C") (pintype "passive"))
      (node (ref "R9") (pin "2") (pinfunction "2_2") (pintype "passive"))
    )
    (net (code "31") (name "Net-(LED10-PadC)") (class "Default")
      (node (ref "LED10") (pin "C") (pinfunction "C_C") (pintype "passive"))
      (node (ref "R10") (pin "2") (pinfunction "2_2") (pintype "passive"))
    )
    (net (code "32") (name "Net-(LED11-PadC)") (class "Default")
      (node (ref "LED11") (pin "C") (pinfunction "C_C") (pintype "passive"))
      (node (ref "R11") (pin "2") (pinfunction "2_2") (pintype "passive"))
    )
    (net (code "33") (name "Net-(LED12-PadC)") (class "Default")
      (node (ref "LED12") (pin "C") (pinfunction "C_C") (pintype "passive"))
      (node (ref "R12") (pin "2") (pinfunction "2_2") (pintype "passive"))
    )
    (net (code "34") (name "Net-(LED13-PadC)") (class "Default")
      (node (ref "LED13") (pin "C") (pinfunction "C_C") (pintype "passive"))
      (node (ref "R13") (pin "2") (pinfunction "2_2") (pintype "passive"))
    )
    (net (code "35") (name "Net-(LED14-PadC)") (class "Default")
      (node (ref "LED14") (pin "C") (pinfunction "C_C") (pintype "passive"))
      (node (ref "R14") (pin "2") (pinfunction "2_2") (pintype "passive"))
    )
    (net (code "36") (name "Net-(LED15-PadC)") (class "Default")
      (node (ref "LED15") (pin "C") (pinfunction "C_C") (pintype "passive"))
      (node (ref "R15") (pin "1") (pinfunction "1_1") (pintype "passive"))
    )
    (net (code "37") (name "Net-(LED16-PadC)") (class "Default")
      (node (ref "LED16") (pin "C") (pinfunction "C_C") (pintype "passive"))
      (node (ref "R16") (pin "1") (pinfunction "1_1") (pintype "passive"))
    )
    (net (code "38") (name "Net-(LED17-PadC)") (class "Default")
      (node (ref "LED17") (pin "C") (pinfunction "C_C") (pintype "passive"))
      (node (ref "R17") (pin "1") (pinfunction "1_1") (pintype "passive"))
    )
    (net (code "39") (name "Net-(LED18-PadC)") (class "Default")
      (node (ref "LED18") (pin "C") (pinfunction "C_C") (pintype "passive"))
      (node (ref "R18") (pin "1") (pinfunction "1_1") (pintype "passive"))
    )
    (net (code "40") (name "Net-(LED19-PadC)") (class "Default")
      (node (ref "LED19") (pin "C") (pinfunction "C_C") (pintype "passive"))
      (node (ref "R19") (pin "2") (pinfunction "2_2") (pintype "passive"))
    )
    (net (code "41") (name "Net-(LED20-PadC)") (class "Default")
      (node (ref "LED20") (pin "C") (pinfunction "C_C") (pintype "passive"))
      (node (ref "R20") (pin "1") (pinfunction "1_1") (pintype "passive"))
    )
    (net (code "42") (name "Net-(LED21-PadC)") (class "Default")
      (node (ref "LED21") (pin "C") (pinfunction "C_C") (pintype "passive"))
      (node (ref "R21") (pin "1") (pinfunction "1_1") (pintype "passive"))
    )
    (net (code "43") (name "Net-(LED22-PadC)") (class "Default")
      (node (ref "LED22") (pin "C") (pinfunction "C_C") (pintype "passive"))
      (node (ref "R22") (pin "1") (pinfunction "1_1") (pintype "passive"))
    )
    (net (code "44") (name "Net-(LED23-PadC)") (class "Default")
      (node (ref "LED23") (pin "C") (pinfunction "C_C") (pintype "passive"))
      (node (ref "R23") (pin "2") (pinfunction "2_2") (pintype "passive"))
    )
    (net (code "45") (name "Net-(MSP430_G2553-Pad2)") (class "Default")
      (node (ref "MSP430_G2553") (pin "2") (pinfunction "2_2") (pintype "bidirectional"))
      (node (ref "SV1") (pin "9") (pinfunction "9_9") (pintype "passive"))
    )
    (net (code "46") (name "Net-(MSP430_G2553-Pad3)") (class "Default")
      (node (ref "MSP430_G2553") (pin "3") (pinfunction "3_3") (pintype "bidirectional"))
      (node (ref "SV1") (pin "8") (pinfunction "8_8") (pintype "passive"))
    )
    (net (code "47") (name "Net-(MSP430_G2553-Pad4)") (class "Default")
      (node (ref "MSP430_G2553") (pin "4") (pinfunction "4_4") (pintype "bidirectional"))
      (node (ref "SV1") (pin "7") (pinfunction "7_7") (pintype "passive"))
    )
    (net (code "48") (name "Net-(MSP430_G2553-Pad5)") (class "Default")
      (node (ref "MSP430_G2553") (pin "5") (pinfunction "5_5") (pintype "bidirectional"))
      (node (ref "SV1") (pin "6") (pinfunction "6_6") (pintype "passive"))
    )
    (net (code "49") (name "Net-(MSP430_G2553-Pad6)") (class "Default")
      (node (ref "MSP430_G2553") (pin "6") (pinfunction "6_6") (pintype "bidirectional"))
      (node (ref "SV1") (pin "5") (pinfunction "5_5") (pintype "passive"))
    )
    (net (code "50") (name "Net-(MSP430_G2553-Pad7)") (class "Default")
      (node (ref "MSP430_G2553") (pin "7") (pinfunction "7_7") (pintype "bidirectional"))
      (node (ref "SV1") (pin "4") (pinfunction "4_4") (pintype "passive"))
    )
    (net (code "51") (name "Net-(MSP430_G2553-Pad8)") (class "Default")
      (node (ref "MSP430_G2553") (pin "8") (pinfunction "8_8") (pintype "bidirectional"))
      (node (ref "SV1") (pin "3") (pinfunction "3_3") (pintype "passive"))
    )
    (net (code "52") (name "Net-(MSP430_G2553-Pad9)") (class "Default")
      (node (ref "MSP430_G2553") (pin "9") (pinfunction "9_9") (pintype "bidirectional"))
      (node (ref "SV1") (pin "2") (pinfunction "2_2") (pintype "passive"))
    )
    (net (code "53") (name "Net-(MSP430_G2553-Pad10)") (class "Default")
      (node (ref "MSP430_G2553") (pin "10") (pinfunction "10_10") (pintype "bidirectional"))
      (node (ref "SV1") (pin "1") (pinfunction "1_1") (pintype "passive"))
    )
    (net (code "54") (name "Net-(MSP430_G2553-Pad11)") (class "Default")
      (node (ref "MSP430_G2553") (pin "11") (pinfunction "11_11") (pintype "bidirectional"))
      (node (ref "SV2") (pin "10") (pinfunction "10_10") (pintype "passive"))
    )
    (net (code "55") (name "Net-(MSP430_G2553-Pad12)") (class "Default")
      (node (ref "MSP430_G2553") (pin "12") (pinfunction "12_12") (pintype "bidirectional"))
      (node (ref "SV2") (pin "9") (pinfunction "9_9") (pintype "passive"))
    )
    (net (code "56") (name "Net-(MSP430_G2553-Pad13)") (class "Default")
      (node (ref "MSP430_G2553") (pin "13") (pinfunction "13_13") (pintype "bidirectional"))
      (node (ref "SV2") (pin "8") (pinfunction "8_8") (pintype "passive"))
    )
    (net (code "57") (name "Net-(MSP430_G2553-Pad14)") (class "Default")
      (node (ref "MSP430_G2553") (pin "14") (pinfunction "14_14") (pintype "bidirectional"))
      (node (ref "SV2") (pin "7") (pinfunction "7_7") (pintype "passive"))
    )
    (net (code "58") (name "Net-(MSP430_G2553-Pad15)") (class "Default")
      (node (ref "MSP430_G2553") (pin "15") (pinfunction "15_15") (pintype "bidirectional"))
      (node (ref "SV2") (pin "6") (pinfunction "6_6") (pintype "passive"))
    )
    (net (code "59") (name "Net-(MSP430_G2553-Pad18)") (class "Default")
      (node (ref "MSP430_G2553") (pin "18") (pinfunction "18_18") (pintype "bidirectional"))
      (node (ref "SV2") (pin "3") (pinfunction "3_3") (pintype "passive"))
    )
    (net (code "60") (name "Net-(MSP430_G2553-Pad19)") (class "Default")
      (node (ref "MSP430_G2553") (pin "19") (pinfunction "19_19") (pintype "bidirectional"))
      (node (ref "SV2") (pin "2") (pinfunction "2_2") (pintype "passive"))
    )
    (net (code "61") (name "Net-(U$3-1_CP1)") (class "Default")
      (node (ref "1_CP1") (pin "TP") (pinfunction "TP_TP") (pintype "input"))
      (node (ref "CP") (pin "2") (pinfunction "2_2") (pintype "passive"))
      (node (ref "U$3") (pin "1") (pinfunction "1_CP1_1") (pintype "bidirectional"))
    )
    (net (code "62") (name "Net-(U$3-2_CP2)") (class "Default")
      (node (ref "2_CP2") (pin "TP") (pinfunction "TP_TP") (pintype "input"))
      (node (ref "CP") (pin "1") (pinfunction "1_1") (pintype "passive"))
      (node (ref "U$3") (pin "2") (pinfunction "2_CP2_2") (pintype "bidirectional"))
    )
    (net (code "63") (name "Net-(U$3-3_VCP)") (class "Default")
      (node (ref "3_VCP") (pin "TP") (pinfunction "TP_TP") (pintype "input"))
      (node (ref "U$3") (pin "3") (pinfunction "3_VCP_3") (pintype "bidirectional"))
      (node (ref "VCP") (pin "2") (pinfunction "2_2") (pintype "passive"))
    )
    (net (code "64") (name "Net-(U$3-7_VINT)") (class "Default")
      (node (ref "7_VINT") (pin "TP") (pinfunction "TP_TP") (pintype "input"))
      (node (ref "C4") (pin "2") (pinfunction "2_2") (pintype "passive"))
      (node (ref "U$3") (pin "7") (pinfunction "7_VINT_7") (pintype "bidirectional"))
    )
    (net (code "65") (name "RESET") (class "Default")
      (node (ref "9_RESET") (pin "TP") (pinfunction "TP_TP") (pintype "input"))
      (node (ref "LED9") (pin "A") (pinfunction "A_A") (pintype "passive"))
      (node (ref "OTHER") (pin "2") (pinfunction "2_2") (pintype "passive"))
      (node (ref "U$3") (pin "9") (pinfunction "9_RESET_9") (pintype "bidirectional"))
    )
    (net (code "66") (name "RST") (class "Default")
      (node (ref "LED14") (pin "A") (pinfunction "A_A") (pintype "passive"))
      (node (ref "MSP430") (pin "3") (pinfunction "3_3") (pintype "passive"))
      (node (ref "MSP430_G2553") (pin "16") (pinfunction "16_16") (pintype "bidirectional"))
      (node (ref "SV2") (pin "5") (pinfunction "5_5") (pintype "passive"))
    )
    (net (code "67") (name "SCLK") (class "Default")
      (node (ref "14_SCLK") (pin "TP") (pinfunction "TP_TP") (pintype "input"))
      (node (ref "LED1") (pin "A") (pinfunction "A_A") (pintype "passive"))
      (node (ref "SPI") (pin "1") (pinfunction "1_1") (pintype "passive"))
      (node (ref "U$3") (pin "14") (pinfunction "14_SCLK_14") (pintype "bidirectional"))
    )
    (net (code "68") (name "SCS") (class "Default")
      (node (ref "16_SCS") (pin "TP") (pinfunction "TP_TP") (pintype "input"))
      (node (ref "LED3") (pin "A") (pinfunction "A_A") (pintype "passive"))
      (node (ref "SPI") (pin "3") (pinfunction "3_3") (pintype "passive"))
      (node (ref "U$3") (pin "16") (pinfunction "16_SCS_16") (pintype "bidirectional"))
    )
    (net (code "69") (name "SDATAI") (class "Default")
      (node (ref "15_SDATAI") (pin "TP") (pinfunction "TP_TP") (pintype "input"))
      (node (ref "LED2") (pin "A") (pinfunction "A_A") (pintype "passive"))
      (node (ref "SPI") (pin "2") (pinfunction "2_2") (pintype "passive"))
      (node (ref "U$3") (pin "15") (pinfunction "15_SDATI_15") (pintype "bidirectional"))
    )
    (net (code "70") (name "SDATAO") (class "Default")
      (node (ref "17_SDATAO") (pin "TP") (pinfunction "TP_TP") (pintype "input"))
      (node (ref "LED4") (pin "A") (pinfunction "A_A") (pintype "passive"))
      (node (ref "SPI") (pin "4") (pinfunction "4_4") (pintype "passive"))
      (node (ref "U$3") (pin "17") (pinfunction "17_SDATAO_17") (pintype "bidirectional"))
    )
    (net (code "71") (name "SLEEPN") (class "Default")
      (node (ref "8_SLEEPN") (pin "TP") (pinfunction "TP_TP") (pintype "input"))
      (node (ref "LED8") (pin "A") (pinfunction "A_A") (pintype "passive"))
      (node (ref "OTHER") (pin "1") (pinfunction "1_1") (pintype "passive"))
      (node (ref "U$3") (pin "8") (pinfunction "8_SLEEPN_8") (pintype "bidirectional"))
    )
    (net (code "72") (name "TEST") (class "Default")
      (node (ref "LED13") (pin "A") (pinfunction "A_A") (pintype "passive"))
      (node (ref "MSP430") (pin "2") (pinfunction "2_2") (pintype "passive"))
      (node (ref "MSP430_G2553") (pin "17") (pinfunction "17_17") (pintype "bidirectional"))
      (node (ref "SV2") (pin "4") (pinfunction "4_4") (pintype "passive"))
    )
    (net (code "73") (name "VCC") (class "Default")
      (node (ref "4_VM") (pin "TP") (pinfunction "TP_TP") (pintype "input"))
      (node (ref "A1HS") (pin "2") (pinfunction "D_2") (pintype "bidirectional"))
      (node (ref "A2HS") (pin "2") (pinfunction "D_2") (pintype "bidirectional"))
      (node (ref "AUX") (pin "P$2") (pinfunction "+_P$2") (pintype "passive"))
      (node (ref "B1HS") (pin "2") (pinfunction "D_2") (pintype "bidirectional"))
      (node (ref "B2HS") (pin "2") (pinfunction "D_2") (pintype "bidirectional"))
      (node (ref "BATT") (pin "POS1") (pinfunction "+_POS1") (pintype "passive"))
      (node (ref "BATT") (pin "POS2") (pinfunction "+_POS2") (pintype "passive"))
      (node (ref "BATT") (pin "POS3") (pinfunction "+_POS3") (pintype "passive"))
      (node (ref "C5") (pin "2") (pinfunction "2_2") (pintype "passive"))
      (node (ref "U$1") (pin "+") (pinfunction "+_+") (pintype "passive"))
      (node (ref "U$16") (pin "+") (pinfunction "+_+") (pintype "passive"))
      (node (ref "U$2") (pin "+") (pinfunction "+_+") (pintype "passive"))
      (node (ref "U$3") (pin "4") (pinfunction "4_VM_4") (pintype "bidirectional"))
      (node (ref "VCP") (pin "1") (pinfunction "1_1") (pintype "passive"))
      (node (ref "VOLTAGE") (pin "1") (pinfunction "1_1") (pintype "passive"))
    )
    (net (code "74") (name "V_MSP430") (class "Default")
      (node (ref "LED12") (pin "A") (pinfunction "A_A") (pintype "passive"))
      (node (ref "MSP430") (pin "1") (pinfunction "1_1") (pintype "passive"))
      (node (ref "MSP430_G2553") (pin "1") (pinfunction "1_1") (pintype "bidirectional"))
      (node (ref "SV1") (pin "10") (pinfunction "10_10") (pintype "passive"))
    )
    (net (code "75") (name "unconnected-(U$3-20_RSVD-Pad20)") (class "Default")
      (node (ref "U$3") (pin "20") (pinfunction "20_RSVD_20") (pintype "bidirectional"))
    )
    (net (code "76") (name "unconnected-(VOLTAGE-Pad2)") (class "Default")
      (node (ref "VOLTAGE") (pin "2") (pinfunction "2_2") (pintype "passive"))
    )
  )
)
